# 14_FPGA_banks_7A_8A.net
KiCad netlist of a schematic drawn in Altium Designer
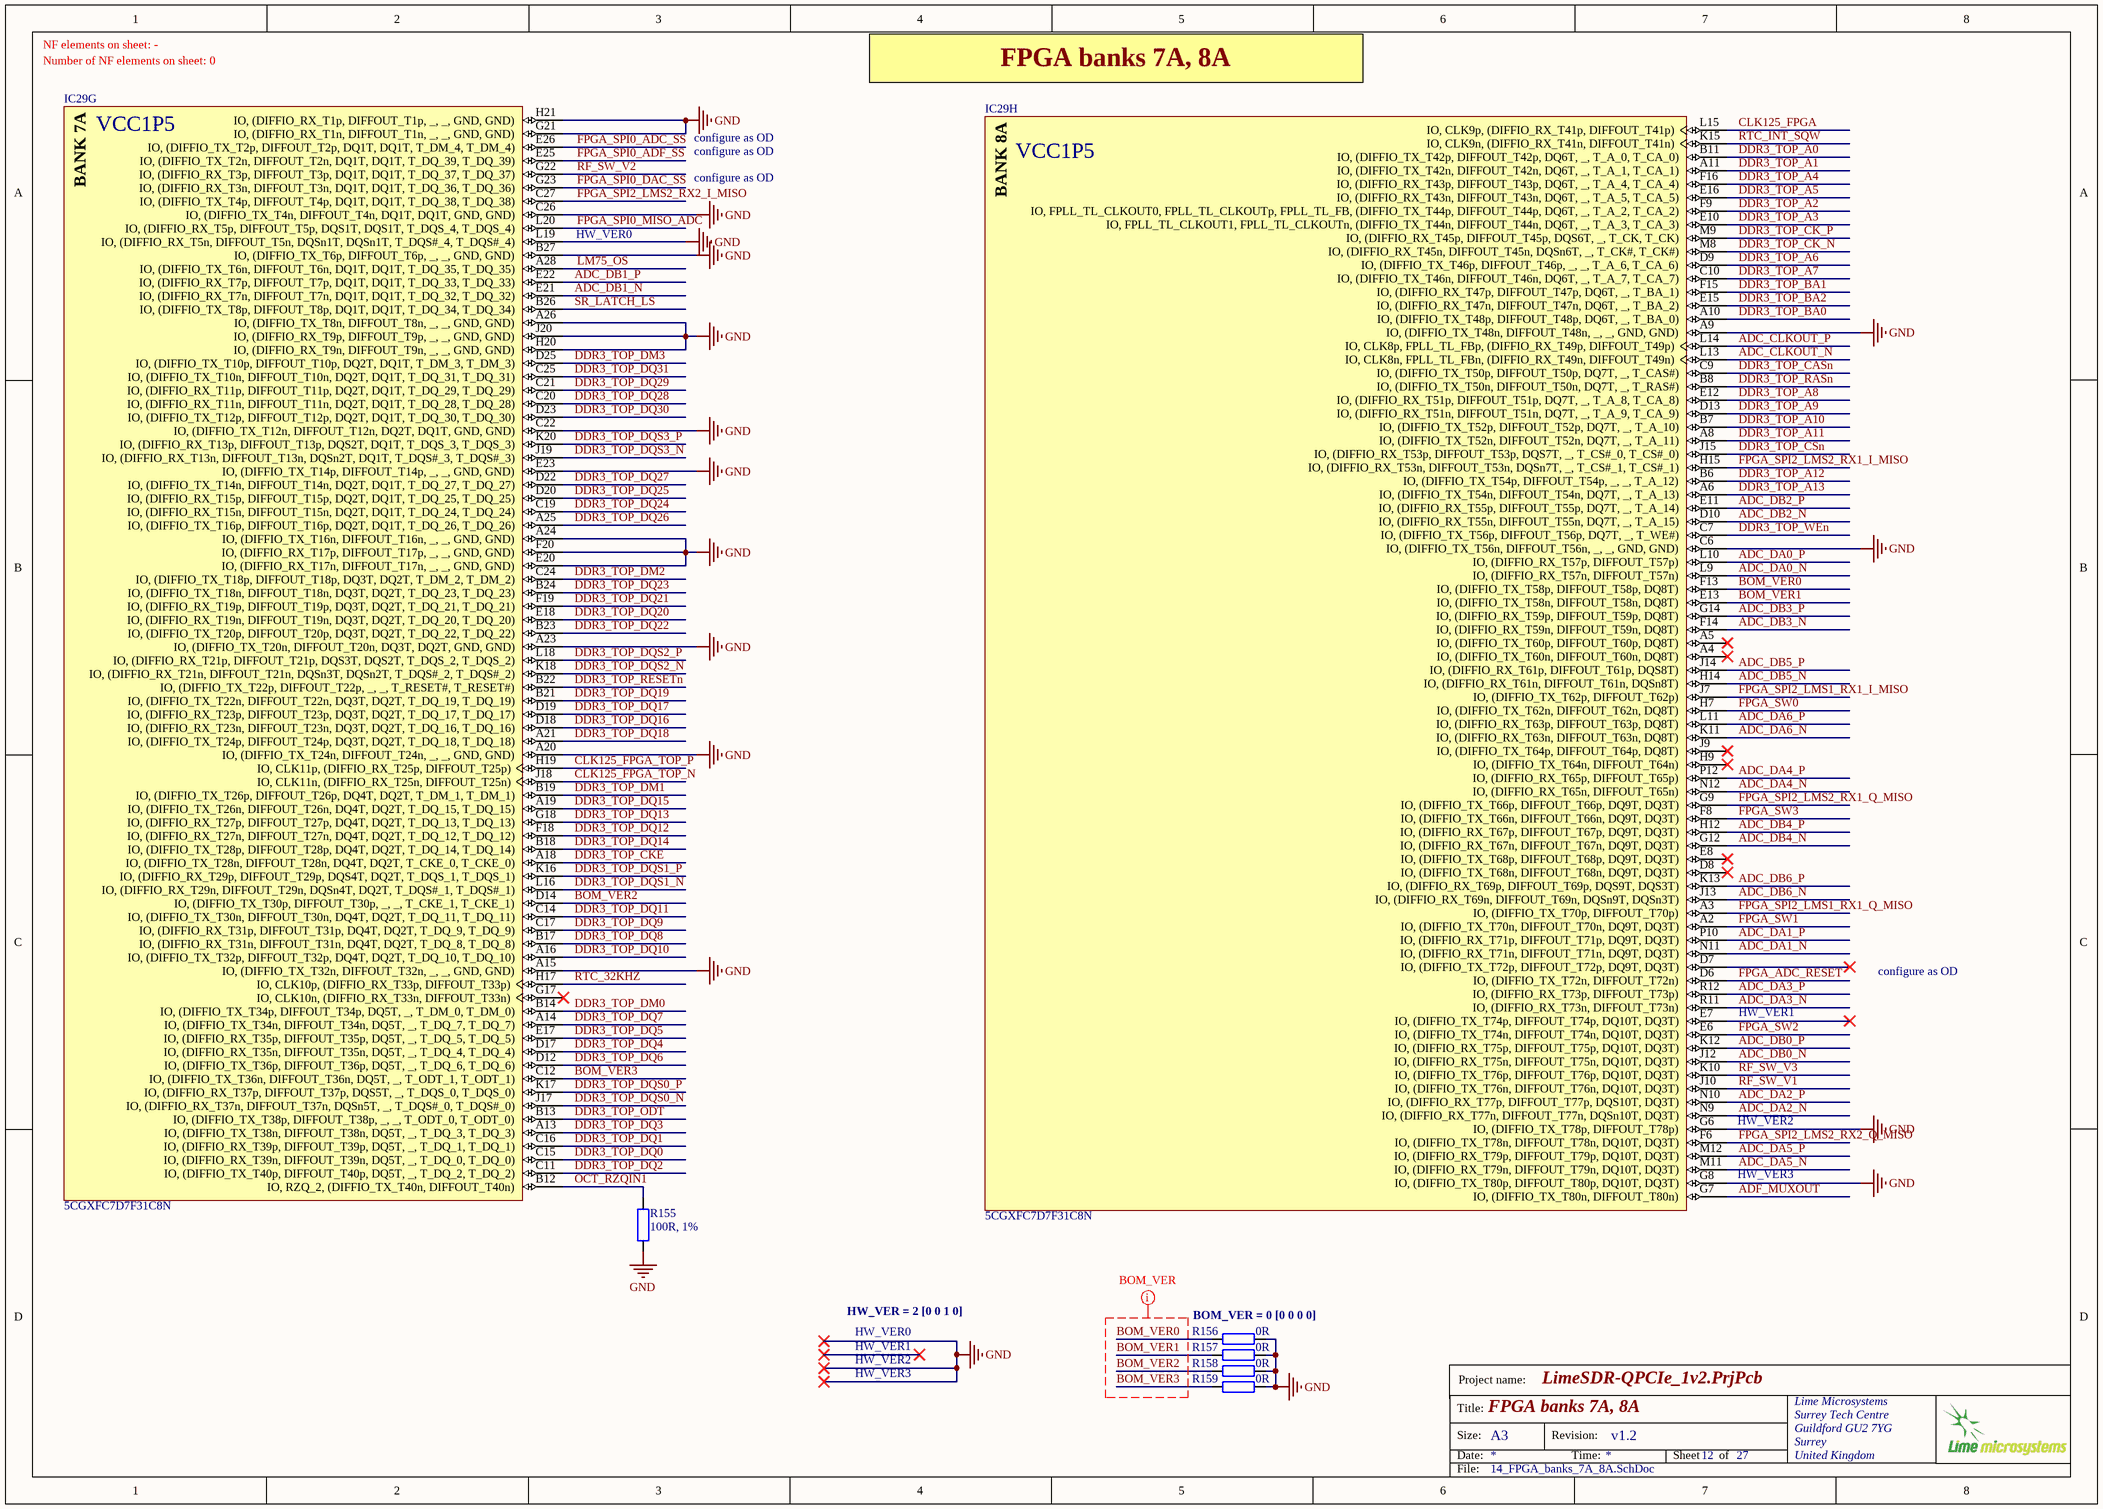
[diagram p0: 14_FPGA_banks_7A_8A.SchDoc]

(export (version "E")
  (design (tool "Eeschema 10.0.6"))
  (components
    (comp (ref "IC29")
      (value "5CGXFC7D7F31C8N")
      (footprint "ALTR-FBGA896_A-200")
      (fields (field (name "MANUFACTURER") "Altera"))
      (libsource (lib "LimeMicroAltiumLib_schLib") (part "5CGXFC7D7F31C8N"))
    )
    (comp (ref "R155")
      (value "100R, 1%")
      (footprint "RES0402")
      (fields (field (name "TOLERANCE") "±1%") (field (name "MANUFACTURER") "Stackpole Electronics Inc."))
      (libsource (lib "LimeFPGAboard_schLib") (part "Res_0402"))
    )
    (comp (ref "R156")
      (value "0R")
      (footprint "RES0402")
      (fields (field (name "MANUFACTURER") "Yageo"))
      (libsource (lib "LimeFPGAboard_schLib") (part "Res_0402"))
    )
    (comp (ref "R157")
      (value "0R")
      (footprint "RES0402")
      (fields (field (name "MANUFACTURER") "Yageo"))
      (libsource (lib "LimeFPGAboard_schLib") (part "Res_0402"))
    )
    (comp (ref "R158")
      (value "0R")
      (footprint "RES0402")
      (fields (field (name "MANUFACTURER") "Yageo"))
      (libsource (lib "LimeFPGAboard_schLib") (part "Res_0402"))
    )
    (comp (ref "R159")
      (value "0R")
      (footprint "RES0402")
      (fields (field (name "MANUFACTURER") "Yageo"))
      (libsource (lib "LimeFPGAboard_schLib") (part "Res_0402"))
    )
  )
  (nets
    (net (code "1") (name "/ADC_CLKOUT_N") (class "Default")
      (node (ref "IC29") (pin "L13") (pinfunction "IO,_CLK8n,_FPLL_TL_FBn,_(DIFFIO_RX_T49n,_DIFFOUT_T49n)_L13") (pintype "bidirectional"))
    )
    (net (code "2") (name "/ADC_CLKOUT_P") (class "Default")
      (node (ref "IC29") (pin "L14") (pinfunction "IO,_CLK8p,_FPLL_TL_FBp,_(DIFFIO_RX_T49p,_DIFFOUT_T49p)_L14") (pintype "bidirectional"))
    )
    (net (code "3") (name "/ADC_DA0_N") (class "Default")
      (node (ref "IC29") (pin "L9") (pinfunction "IO,_(DIFFIO_RX_T57n,_DIFFOUT_T57n)_L9") (pintype "bidirectional"))
    )
    (net (code "4") (name "/ADC_DA0_P") (class "Default")
      (node (ref "IC29") (pin "L10") (pinfunction "IO,_(DIFFIO_RX_T57p,_DIFFOUT_T57p)_L10") (pintype "bidirectional"))
    )
    (net (code "5") (name "/ADC_DA1_N") (class "Default")
      (node (ref "IC29") (pin "N11") (pinfunction "IO,_(DIFFIO_RX_T71n,_DIFFOUT_T71n,_DQ9T,_DQ3T)_N11") (pintype "bidirectional"))
    )
    (net (code "6") (name "/ADC_DA1_P") (class "Default")
      (node (ref "IC29") (pin "P10") (pinfunction "IO,_(DIFFIO_RX_T71p,_DIFFOUT_T71p,_DQ9T,_DQ3T)_P10") (pintype "bidirectional"))
    )
    (net (code "7") (name "/ADC_DA2_N") (class "Default")
      (node (ref "IC29") (pin "N9") (pinfunction "IO,_(DIFFIO_RX_T77n,_DIFFOUT_T77n,_DQSn10T,_DQ3T)_N9") (pintype "bidirectional"))
    )
    (net (code "8") (name "/ADC_DA2_P") (class "Default")
      (node (ref "IC29") (pin "N10") (pinfunction "IO,_(DIFFIO_RX_T77p,_DIFFOUT_T77p,_DQS10T,_DQ3T)_N10") (pintype "bidirectional"))
    )
    (net (code "9") (name "/ADC_DA3_N") (class "Default")
      (node (ref "IC29") (pin "R11") (pinfunction "IO,_(DIFFIO_RX_T73n,_DIFFOUT_T73n)_R11") (pintype "bidirectional"))
    )
    (net (code "10") (name "/ADC_DA3_P") (class "Default")
      (node (ref "IC29") (pin "R12") (pinfunction "IO,_(DIFFIO_RX_T73p,_DIFFOUT_T73p)_R12") (pintype "bidirectional"))
    )
    (net (code "11") (name "/ADC_DA4_N") (class "Default")
      (node (ref "IC29") (pin "N12") (pinfunction "IO,_(DIFFIO_RX_T65n,_DIFFOUT_T65n)_N12") (pintype "bidirectional"))
    )
    (net (code "12") (name "/ADC_DA4_P") (class "Default")
      (node (ref "IC29") (pin "P12") (pinfunction "IO,_(DIFFIO_RX_T65p,_DIFFOUT_T65p)_P12") (pintype "bidirectional"))
    )
    (net (code "13") (name "/ADC_DA5_N") (class "Default")
      (node (ref "IC29") (pin "M11") (pinfunction "IO,_(DIFFIO_RX_T79n,_DIFFOUT_T79n,_DQ10T,_DQ3T)_M11") (pintype "bidirectional"))
    )
    (net (code "14") (name "/ADC_DA5_P") (class "Default")
      (node (ref "IC29") (pin "M12") (pinfunction "IO,_(DIFFIO_RX_T79p,_DIFFOUT_T79p,_DQ10T,_DQ3T)_M12") (pintype "bidirectional"))
    )
    (net (code "15") (name "/ADC_DA6_N") (class "Default")
      (node (ref "IC29") (pin "K11") (pinfunction "IO,_(DIFFIO_RX_T63n,_DIFFOUT_T63n,_DQ8T)_K11") (pintype "bidirectional"))
    )
    (net (code "16") (name "/ADC_DA6_P") (class "Default")
      (node (ref "IC29") (pin "L11") (pinfunction "IO,_(DIFFIO_RX_T63p,_DIFFOUT_T63p,_DQ8T)_L11") (pintype "bidirectional"))
    )
    (net (code "17") (name "/ADC_DB0_N") (class "Default")
      (node (ref "IC29") (pin "J12") (pinfunction "IO,_(DIFFIO_RX_T75n,_DIFFOUT_T75n,_DQ10T,_DQ3T)_J12") (pintype "bidirectional"))
    )
    (net (code "18") (name "/ADC_DB0_P") (class "Default")
      (node (ref "IC29") (pin "K12") (pinfunction "IO,_(DIFFIO_RX_T75p,_DIFFOUT_T75p,_DQ10T,_DQ3T)_K12") (pintype "bidirectional"))
    )
    (net (code "19") (name "/ADC_DB1_N") (class "Default")
      (node (ref "IC29") (pin "E21") (pinfunction "IO,_(DIFFIO_RX_T7n,_DIFFOUT_T7n,_DQ1T,_DQ1T,_T_DQ_32,_T_DQ_32)_E21") (pintype "bidirectional"))
    )
    (net (code "20") (name "/ADC_DB1_P") (class "Default")
      (node (ref "IC29") (pin "E22") (pinfunction "IO,_(DIFFIO_RX_T7p,_DIFFOUT_T7p,_DQ1T,_DQ1T,_T_DQ_33,_T_DQ_33)_E22") (pintype "bidirectional"))
    )
    (net (code "21") (name "/ADC_DB2_N") (class "Default")
      (node (ref "IC29") (pin "D10") (pinfunction "IO,_(DIFFIO_RX_T55n,_DIFFOUT_T55n,_DQ7T,__,_T_A_15)_D10") (pintype "bidirectional"))
    )
    (net (code "22") (name "/ADC_DB2_P") (class "Default")
      (node (ref "IC29") (pin "E11") (pinfunction "IO,_(DIFFIO_RX_T55p,_DIFFOUT_T55p,_DQ7T,__,_T_A_14)_E11") (pintype "bidirectional"))
    )
    (net (code "23") (name "/ADC_DB3_N") (class "Default")
      (node (ref "IC29") (pin "F14") (pinfunction "IO,_(DIFFIO_RX_T59n,_DIFFOUT_T59n,_DQ8T)_F14") (pintype "bidirectional"))
    )
    (net (code "24") (name "/ADC_DB3_P") (class "Default")
      (node (ref "IC29") (pin "G14") (pinfunction "IO,_(DIFFIO_RX_T59p,_DIFFOUT_T59p,_DQ8T)_G14") (pintype "bidirectional"))
    )
    (net (code "25") (name "/ADC_DB4_N") (class "Default")
      (node (ref "IC29") (pin "G12") (pinfunction "IO,_(DIFFIO_RX_T67n,_DIFFOUT_T67n,_DQ9T,_DQ3T)_G12") (pintype "bidirectional"))
    )
    (net (code "26") (name "/ADC_DB4_P") (class "Default")
      (node (ref "IC29") (pin "H12") (pinfunction "IO,_(DIFFIO_RX_T67p,_DIFFOUT_T67p,_DQ9T,_DQ3T)_H12") (pintype "bidirectional"))
    )
    (net (code "27") (name "/ADC_DB5_N") (class "Default")
      (node (ref "IC29") (pin "H14") (pinfunction "IO,_(DIFFIO_RX_T61n,_DIFFOUT_T61n,_DQSn8T)_H14") (pintype "bidirectional"))
    )
    (net (code "28") (name "/ADC_DB5_P") (class "Default")
      (node (ref "IC29") (pin "J14") (pinfunction "IO,_(DIFFIO_RX_T61p,_DIFFOUT_T61p,_DQS8T)_J14") (pintype "bidirectional"))
    )
    (net (code "29") (name "/ADC_DB6_N") (class "Default")
      (node (ref "IC29") (pin "J13") (pinfunction "IO,_(DIFFIO_RX_T69n,_DIFFOUT_T69n,_DQSn9T,_DQSn3T)_J13") (pintype "bidirectional"))
    )
    (net (code "30") (name "/ADC_DB6_P") (class "Default")
      (node (ref "IC29") (pin "K13") (pinfunction "IO,_(DIFFIO_RX_T69p,_DIFFOUT_T69p,_DQS9T,_DQS3T)_K13") (pintype "bidirectional"))
    )
    (net (code "31") (name "/ADF_MUXOUT") (class "Default")
      (node (ref "IC29") (pin "G7") (pinfunction "IO,_(DIFFIO_TX_T80n,_DIFFOUT_T80n)_G7") (pintype "bidirectional"))
    )
    (net (code "32") (name "/BOM_VER0") (class "Default")
      (node (ref "IC29") (pin "F13") (pinfunction "IO,_(DIFFIO_TX_T58p,_DIFFOUT_T58p,_DQ8T)_F13") (pintype "bidirectional"))
      (node (ref "R156") (pin "1") (pinfunction "1_1") (pintype "passive"))
    )
    (net (code "33") (name "/BOM_VER1") (class "Default")
      (node (ref "IC29") (pin "E13") (pinfunction "IO,_(DIFFIO_TX_T58n,_DIFFOUT_T58n,_DQ8T)_E13") (pintype "bidirectional"))
      (node (ref "R157") (pin "1") (pinfunction "1_1") (pintype "passive"))
    )
    (net (code "34") (name "/BOM_VER2") (class "Default")
      (node (ref "IC29") (pin "D14") (pinfunction "IO,_(DIFFIO_TX_T30p,_DIFFOUT_T30p,__,__,_T_CKE_1,_T_CKE_1)_D14") (pintype "bidirectional"))
      (node (ref "R158") (pin "1") (pinfunction "1_1") (pintype "passive"))
    )
    (net (code "35") (name "/BOM_VER3") (class "Default")
      (node (ref "IC29") (pin "C12") (pinfunction "IO,_(DIFFIO_TX_T36n,_DIFFOUT_T36n,_DQ5T,__,_T_ODT_1,_T_ODT_1)_C12") (pintype "bidirectional"))
      (node (ref "R159") (pin "1") (pinfunction "1_1") (pintype "passive"))
    )
    (net (code "36") (name "/CLK125_FPGA") (class "Default")
      (node (ref "IC29") (pin "L15") (pinfunction "IO,_CLK9p,_(DIFFIO_RX_T41p,_DIFFOUT_T41p)_L15") (pintype "bidirectional"))
    )
    (net (code "37") (name "/CLK125_FPGA_TOP_N") (class "Default")
      (node (ref "IC29") (pin "J18") (pinfunction "IO,_CLK11n,_(DIFFIO_RX_T25n,_DIFFOUT_T25n)_J18") (pintype "bidirectional"))
    )
    (net (code "38") (name "/CLK125_FPGA_TOP_P") (class "Default")
      (node (ref "IC29") (pin "H19") (pinfunction "IO,_CLK11p,_(DIFFIO_RX_T25p,_DIFFOUT_T25p)_H19") (pintype "bidirectional"))
    )
    (net (code "39") (name "/DDR3_TOP_A0") (class "Default")
      (node (ref "IC29") (pin "B11") (pinfunction "IO,_(DIFFIO_TX_T42p,_DIFFOUT_T42p,_DQ6T,__,_T_A_0,_T_CA_0)_B11") (pintype "bidirectional"))
    )
    (net (code "40") (name "/DDR3_TOP_A1") (class "Default")
      (node (ref "IC29") (pin "A11") (pinfunction "IO,_(DIFFIO_TX_T42n,_DIFFOUT_T42n,_DQ6T,__,_T_A_1,_T_CA_1)_A11") (pintype "bidirectional"))
    )
    (net (code "41") (name "/DDR3_TOP_A2") (class "Default")
      (node (ref "IC29") (pin "F9") (pinfunction "IO,_FPLL_TL_CLKOUT0,_FPLL_TL_CLKOUTp,_FPLL_TL_FB,_(DIFFIO_TX_T44p,_DIFFOUT_T44p,_DQ6T,__,_T_A_2,_T_CA_2)_F9") (pintype "bidirectional"))
    )
    (net (code "42") (name "/DDR3_TOP_A3") (class "Default")
      (node (ref "IC29") (pin "E10") (pinfunction "IO,_FPLL_TL_CLKOUT1,_FPLL_TL_CLKOUTn,_(DIFFIO_TX_T44n,_DIFFOUT_T44n,_DQ6T,__,_T_A_3,_T_CA_3)_E10") (pintype "bidirectional"))
    )
    (net (code "43") (name "/DDR3_TOP_A4") (class "Default")
      (node (ref "IC29") (pin "F16") (pinfunction "IO,_(DIFFIO_RX_T43p,_DIFFOUT_T43p,_DQ6T,__,_T_A_4,_T_CA_4)_F16") (pintype "bidirectional"))
    )
    (net (code "44") (name "/DDR3_TOP_A5") (class "Default")
      (node (ref "IC29") (pin "E16") (pinfunction "IO,_(DIFFIO_RX_T43n,_DIFFOUT_T43n,_DQ6T,__,_T_A_5,_T_CA_5)_E16") (pintype "bidirectional"))
    )
    (net (code "45") (name "/DDR3_TOP_A6") (class "Default")
      (node (ref "IC29") (pin "D9") (pinfunction "IO,_(DIFFIO_TX_T46p,_DIFFOUT_T46p,__,__,_T_A_6,_T_CA_6)_D9") (pintype "bidirectional"))
    )
    (net (code "46") (name "/DDR3_TOP_A7") (class "Default")
      (node (ref "IC29") (pin "C10") (pinfunction "IO,_(DIFFIO_TX_T46n,_DIFFOUT_T46n,_DQ6T,__,_T_A_7,_T_CA_7)_C10") (pintype "bidirectional"))
    )
    (net (code "47") (name "/DDR3_TOP_A8") (class "Default")
      (node (ref "IC29") (pin "E12") (pinfunction "IO,_(DIFFIO_RX_T51p,_DIFFOUT_T51p,_DQ7T,__,_T_A_8,_T_CA_8)_E12") (pintype "bidirectional"))
    )
    (net (code "48") (name "/DDR3_TOP_A9") (class "Default")
      (node (ref "IC29") (pin "D13") (pinfunction "IO,_(DIFFIO_RX_T51n,_DIFFOUT_T51n,_DQ7T,__,_T_A_9,_T_CA_9)_D13") (pintype "bidirectional"))
    )
    (net (code "49") (name "/DDR3_TOP_A10") (class "Default")
      (node (ref "IC29") (pin "B7") (pinfunction "IO,_(DIFFIO_TX_T52p,_DIFFOUT_T52p,_DQ7T,__,_T_A_10)_B7") (pintype "bidirectional"))
    )
    (net (code "50") (name "/DDR3_TOP_A11") (class "Default")
      (node (ref "IC29") (pin "A8") (pinfunction "IO,_(DIFFIO_TX_T52n,_DIFFOUT_T52n,_DQ7T,__,_T_A_11)_A8") (pintype "bidirectional"))
    )
    (net (code "51") (name "/DDR3_TOP_A12") (class "Default")
      (node (ref "IC29") (pin "B6") (pinfunction "IO,_(DIFFIO_TX_T54p,_DIFFOUT_T54p,__,__,_T_A_12)_B6") (pintype "bidirectional"))
    )
    (net (code "52") (name "/DDR3_TOP_A13") (class "Default")
      (node (ref "IC29") (pin "A6") (pinfunction "IO,_(DIFFIO_TX_T54n,_DIFFOUT_T54n,_DQ7T,__,_T_A_13)_A6") (pintype "bidirectional"))
    )
    (net (code "53") (name "/DDR3_TOP_BA0") (class "Default")
      (node (ref "IC29") (pin "A10") (pinfunction "IO,_(DIFFIO_TX_T48p,_DIFFOUT_T48p,_DQ6T,__,_T_BA_0)_A10") (pintype "bidirectional"))
    )
    (net (code "54") (name "/DDR3_TOP_BA1") (class "Default")
      (node (ref "IC29") (pin "F15") (pinfunction "IO,_(DIFFIO_RX_T47p,_DIFFOUT_T47p,_DQ6T,__,_T_BA_1)_F15") (pintype "bidirectional"))
    )
    (net (code "55") (name "/DDR3_TOP_BA2") (class "Default")
      (node (ref "IC29") (pin "E15") (pinfunction "IO,_(DIFFIO_RX_T47n,_DIFFOUT_T47n,_DQ6T,__,_T_BA_2)_E15") (pintype "bidirectional"))
    )
    (net (code "56") (name "/DDR3_TOP_CASn") (class "Default")
      (node (ref "IC29") (pin "C9") (pinfunction "IO,_(DIFFIO_TX_T50p,_DIFFOUT_T50p,_DQ7T,__,_T_CAS#)_C9") (pintype "bidirectional"))
    )
    (net (code "57") (name "/DDR3_TOP_CKE") (class "Default")
      (node (ref "IC29") (pin "A18") (pinfunction "IO,_(DIFFIO_TX_T28n,_DIFFOUT_T28n,_DQ4T,_DQ2T,_T_CKE_0,_T_CKE_0)_A18") (pintype "bidirectional"))
    )
    (net (code "58") (name "/DDR3_TOP_CK_N") (class "Default")
      (node (ref "IC29") (pin "M8") (pinfunction "IO,_(DIFFIO_RX_T45n,_DIFFOUT_T45n,_DQSn6T,__,_T_CK#,_T_CK#)_M8") (pintype "bidirectional"))
    )
    (net (code "59") (name "/DDR3_TOP_CK_P") (class "Default")
      (node (ref "IC29") (pin "M9") (pinfunction "IO,_(DIFFIO_RX_T45p,_DIFFOUT_T45p,_DQS6T,__,_T_CK,_T_CK)_M9") (pintype "bidirectional"))
    )
    (net (code "60") (name "/DDR3_TOP_CSn") (class "Default")
      (node (ref "IC29") (pin "J15") (pinfunction "IO,_(DIFFIO_RX_T53p,_DIFFOUT_T53p,_DQS7T,__,_T_CS#_0,_T_CS#_0)_J15") (pintype "bidirectional"))
    )
    (net (code "61") (name "/DDR3_TOP_DM0") (class "Default")
      (node (ref "IC29") (pin "B14") (pinfunction "IO,_(DIFFIO_TX_T34p,_DIFFOUT_T34p,_DQ5T,__,_T_DM_0,_T_DM_0)_B14") (pintype "bidirectional"))
    )
    (net (code "62") (name "/DDR3_TOP_DM1") (class "Default")
      (node (ref "IC29") (pin "B19") (pinfunction "IO,_(DIFFIO_TX_T26p,_DIFFOUT_T26p,_DQ4T,_DQ2T,_T_DM_1,_T_DM_1)_B19") (pintype "bidirectional"))
    )
    (net (code "63") (name "/DDR3_TOP_DM2") (class "Default")
      (node (ref "IC29") (pin "C24") (pinfunction "IO,_(DIFFIO_TX_T18p,_DIFFOUT_T18p,_DQ3T,_DQ2T,_T_DM_2,_T_DM_2)_C24") (pintype "bidirectional"))
    )
    (net (code "64") (name "/DDR3_TOP_DM3") (class "Default")
      (node (ref "IC29") (pin "D25") (pinfunction "IO,_(DIFFIO_TX_T10p,_DIFFOUT_T10p,_DQ2T,_DQ1T,_T_DM_3,_T_DM_3)_D25") (pintype "bidirectional"))
    )
    (net (code "65") (name "/DDR3_TOP_DQ0") (class "Default")
      (node (ref "IC29") (pin "C15") (pinfunction "IO,_(DIFFIO_RX_T39n,_DIFFOUT_T39n,_DQ5T,__,_T_DQ_0,_T_DQ_0)_C15") (pintype "bidirectional"))
    )
    (net (code "66") (name "/DDR3_TOP_DQ1") (class "Default")
      (node (ref "IC29") (pin "C16") (pinfunction "IO,_(DIFFIO_RX_T39p,_DIFFOUT_T39p,_DQ5T,__,_T_DQ_1,_T_DQ_1)_C16") (pintype "bidirectional"))
    )
    (net (code "67") (name "/DDR3_TOP_DQ2") (class "Default")
      (node (ref "IC29") (pin "C11") (pinfunction "IO,_(DIFFIO_TX_T40p,_DIFFOUT_T40p,_DQ5T,__,_T_DQ_2,_T_DQ_2)_C11") (pintype "bidirectional"))
    )
    (net (code "68") (name "/DDR3_TOP_DQ3") (class "Default")
      (node (ref "IC29") (pin "A13") (pinfunction "IO,_(DIFFIO_TX_T38n,_DIFFOUT_T38n,_DQ5T,__,_T_DQ_3,_T_DQ_3)_A13") (pintype "bidirectional"))
    )
    (net (code "69") (name "/DDR3_TOP_DQ4") (class "Default")
      (node (ref "IC29") (pin "D17") (pinfunction "IO,_(DIFFIO_RX_T35n,_DIFFOUT_T35n,_DQ5T,__,_T_DQ_4,_T_DQ_4)_D17") (pintype "bidirectional"))
    )
    (net (code "70") (name "/DDR3_TOP_DQ5") (class "Default")
      (node (ref "IC29") (pin "E17") (pinfunction "IO,_(DIFFIO_RX_T35p,_DIFFOUT_T35p,_DQ5T,__,_T_DQ_5,_T_DQ_5)_E17") (pintype "bidirectional"))
    )
    (net (code "71") (name "/DDR3_TOP_DQ6") (class "Default")
      (node (ref "IC29") (pin "D12") (pinfunction "IO,_(DIFFIO_TX_T36p,_DIFFOUT_T36p,_DQ5T,__,_T_DQ_6,_T_DQ_6)_D12") (pintype "bidirectional"))
    )
    (net (code "72") (name "/DDR3_TOP_DQ7") (class "Default")
      (node (ref "IC29") (pin "A14") (pinfunction "IO,_(DIFFIO_TX_T34n,_DIFFOUT_T34n,_DQ5T,__,_T_DQ_7,_T_DQ_7)_A14") (pintype "bidirectional"))
    )
    (net (code "73") (name "/DDR3_TOP_DQ8") (class "Default")
      (node (ref "IC29") (pin "B17") (pinfunction "IO,_(DIFFIO_RX_T31n,_DIFFOUT_T31n,_DQ4T,_DQ2T,_T_DQ_8,_T_DQ_8)_B17") (pintype "bidirectional"))
    )
    (net (code "74") (name "/DDR3_TOP_DQ9") (class "Default")
      (node (ref "IC29") (pin "C17") (pinfunction "IO,_(DIFFIO_RX_T31p,_DIFFOUT_T31p,_DQ4T,_DQ2T,_T_DQ_9,_T_DQ_9)_C17") (pintype "bidirectional"))
    )
    (net (code "75") (name "/DDR3_TOP_DQ10") (class "Default")
      (node (ref "IC29") (pin "A16") (pinfunction "IO,_(DIFFIO_TX_T32p,_DIFFOUT_T32p,_DQ4T,_DQ2T,_T_DQ_10,_T_DQ_10)_A16") (pintype "bidirectional"))
    )
    (net (code "76") (name "/DDR3_TOP_DQ11") (class "Default")
      (node (ref "IC29") (pin "C14") (pinfunction "IO,_(DIFFIO_TX_T30n,_DIFFOUT_T30n,_DQ4T,_DQ2T,_T_DQ_11,_T_DQ_11)_C14") (pintype "bidirectional"))
    )
    (net (code "77") (name "/DDR3_TOP_DQ12") (class "Default")
      (node (ref "IC29") (pin "F18") (pinfunction "IO,_(DIFFIO_RX_T27n,_DIFFOUT_T27n,_DQ4T,_DQ2T,_T_DQ_12,_T_DQ_12)_F18") (pintype "bidirectional"))
    )
    (net (code "78") (name "/DDR3_TOP_DQ13") (class "Default")
      (node (ref "IC29") (pin "G18") (pinfunction "IO,_(DIFFIO_RX_T27p,_DIFFOUT_T27p,_DQ4T,_DQ2T,_T_DQ_13,_T_DQ_13)_G18") (pintype "bidirectional"))
    )
    (net (code "79") (name "/DDR3_TOP_DQ14") (class "Default")
      (node (ref "IC29") (pin "B18") (pinfunction "IO,_(DIFFIO_TX_T28p,_DIFFOUT_T28p,_DQ4T,_DQ2T,_T_DQ_14,_T_DQ_14)_B18") (pintype "bidirectional"))
    )
    (net (code "80") (name "/DDR3_TOP_DQ15") (class "Default")
      (node (ref "IC29") (pin "A19") (pinfunction "IO,_(DIFFIO_TX_T26n,_DIFFOUT_T26n,_DQ4T,_DQ2T,_T_DQ_15,_T_DQ_15)_A19") (pintype "bidirectional"))
    )
    (net (code "81") (name "/DDR3_TOP_DQ16") (class "Default")
      (node (ref "IC29") (pin "D18") (pinfunction "IO,_(DIFFIO_RX_T23n,_DIFFOUT_T23n,_DQ3T,_DQ2T,_T_DQ_16,_T_DQ_16)_D18") (pintype "bidirectional"))
    )
    (net (code "82") (name "/DDR3_TOP_DQ17") (class "Default")
      (node (ref "IC29") (pin "D19") (pinfunction "IO,_(DIFFIO_RX_T23p,_DIFFOUT_T23p,_DQ3T,_DQ2T,_T_DQ_17,_T_DQ_17)_D19") (pintype "bidirectional"))
    )
    (net (code "83") (name "/DDR3_TOP_DQ18") (class "Default")
      (node (ref "IC29") (pin "A21") (pinfunction "IO,_(DIFFIO_TX_T24p,_DIFFOUT_T24p,_DQ3T,_DQ2T,_T_DQ_18,_T_DQ_18)_A21") (pintype "bidirectional"))
    )
    (net (code "84") (name "/DDR3_TOP_DQ19") (class "Default")
      (node (ref "IC29") (pin "B21") (pinfunction "IO,_(DIFFIO_TX_T22n,_DIFFOUT_T22n,_DQ3T,_DQ2T,_T_DQ_19,_T_DQ_19)_B21") (pintype "bidirectional"))
    )
    (net (code "85") (name "/DDR3_TOP_DQ20") (class "Default")
      (node (ref "IC29") (pin "E18") (pinfunction "IO,_(DIFFIO_RX_T19n,_DIFFOUT_T19n,_DQ3T,_DQ2T,_T_DQ_20,_T_DQ_20)_E18") (pintype "bidirectional"))
    )
    (net (code "86") (name "/DDR3_TOP_DQ21") (class "Default")
      (node (ref "IC29") (pin "F19") (pinfunction "IO,_(DIFFIO_RX_T19p,_DIFFOUT_T19p,_DQ3T,_DQ2T,_T_DQ_21,_T_DQ_21)_F19") (pintype "bidirectional"))
    )
    (net (code "87") (name "/DDR3_TOP_DQ22") (class "Default")
      (node (ref "IC29") (pin "B23") (pinfunction "IO,_(DIFFIO_TX_T20p,_DIFFOUT_T20p,_DQ3T,_DQ2T,_T_DQ_22,_T_DQ_22)_B23") (pintype "bidirectional"))
    )
    (net (code "88") (name "/DDR3_TOP_DQ23") (class "Default")
      (node (ref "IC29") (pin "B24") (pinfunction "IO,_(DIFFIO_TX_T18n,_DIFFOUT_T18n,_DQ3T,_DQ2T,_T_DQ_23,_T_DQ_23)_B24") (pintype "bidirectional"))
    )
    (net (code "89") (name "/DDR3_TOP_DQ24") (class "Default")
      (node (ref "IC29") (pin "C19") (pinfunction "IO,_(DIFFIO_RX_T15n,_DIFFOUT_T15n,_DQ2T,_DQ1T,_T_DQ_24,_T_DQ_24)_C19") (pintype "bidirectional"))
    )
    (net (code "90") (name "/DDR3_TOP_DQ25") (class "Default")
      (node (ref "IC29") (pin "D20") (pinfunction "IO,_(DIFFIO_RX_T15p,_DIFFOUT_T15p,_DQ2T,_DQ1T,_T_DQ_25,_T_DQ_25)_D20") (pintype "bidirectional"))
    )
    (net (code "91") (name "/DDR3_TOP_DQ26") (class "Default")
      (node (ref "IC29") (pin "A25") (pinfunction "IO,_(DIFFIO_TX_T16p,_DIFFOUT_T16p,_DQ2T,_DQ1T,_T_DQ_26,_T_DQ_26)_A25") (pintype "bidirectional"))
    )
    (net (code "92") (name "/DDR3_TOP_DQ27") (class "Default")
      (node (ref "IC29") (pin "D22") (pinfunction "IO,_(DIFFIO_TX_T14n,_DIFFOUT_T14n,_DQ2T,_DQ1T,_T_DQ_27,_T_DQ_27)_D22") (pintype "bidirectional"))
    )
    (net (code "93") (name "/DDR3_TOP_DQ28") (class "Default")
      (node (ref "IC29") (pin "C20") (pinfunction "IO,_(DIFFIO_RX_T11n,_DIFFOUT_T11n,_DQ2T,_DQ1T,_T_DQ_28,_T_DQ_28)_C20") (pintype "bidirectional"))
    )
    (net (code "94") (name "/DDR3_TOP_DQ29") (class "Default")
      (node (ref "IC29") (pin "C21") (pinfunction "IO,_(DIFFIO_RX_T11p,_DIFFOUT_T11p,_DQ2T,_DQ1T,_T_DQ_29,_T_DQ_29)_C21") (pintype "bidirectional"))
    )
    (net (code "95") (name "/DDR3_TOP_DQ30") (class "Default")
      (node (ref "IC29") (pin "D23") (pinfunction "IO,_(DIFFIO_TX_T12p,_DIFFOUT_T12p,_DQ2T,_DQ1T,_T_DQ_30,_T_DQ_30)_D23") (pintype "bidirectional"))
    )
    (net (code "96") (name "/DDR3_TOP_DQ31") (class "Default")
      (node (ref "IC29") (pin "C25") (pinfunction "IO,_(DIFFIO_TX_T10n,_DIFFOUT_T10n,_DQ2T,_DQ1T,_T_DQ_31,_T_DQ_31)_C25") (pintype "bidirectional"))
    )
    (net (code "97") (name "/DDR3_TOP_DQS0_N") (class "Default")
      (node (ref "IC29") (pin "J17") (pinfunction "IO,_(DIFFIO_RX_T37n,_DIFFOUT_T37n,_DQSn5T,__,_T_DQS#_0,_T_DQS#_0)_J17") (pintype "bidirectional"))
    )
    (net (code "98") (name "/DDR3_TOP_DQS0_P") (class "Default")
      (node (ref "IC29") (pin "K17") (pinfunction "IO,_(DIFFIO_RX_T37p,_DIFFOUT_T37p,_DQS5T,__,_T_DQS_0,_T_DQS_0)_K17") (pintype "bidirectional"))
    )
    (net (code "99") (name "/DDR3_TOP_DQS1_N") (class "Default")
      (node (ref "IC29") (pin "L16") (pinfunction "IO,_(DIFFIO_RX_T29n,_DIFFOUT_T29n,_DQSn4T,_DQ2T,_T_DQS#_1,_T_DQS#_1)_L16") (pintype "bidirectional"))
    )
    (net (code "100") (name "/DDR3_TOP_DQS1_P") (class "Default")
      (node (ref "IC29") (pin "K16") (pinfunction "IO,_(DIFFIO_RX_T29p,_DIFFOUT_T29p,_DQS4T,_DQ2T,_T_DQS_1,_T_DQS_1)_K16") (pintype "bidirectional"))
    )
    (net (code "101") (name "/DDR3_TOP_DQS2_N") (class "Default")
      (node (ref "IC29") (pin "K18") (pinfunction "IO,_(DIFFIO_RX_T21n,_DIFFOUT_T21n,_DQSn3T,_DQSn2T,_T_DQS#_2,_T_DQS#_2)_K18") (pintype "bidirectional"))
    )
    (net (code "102") (name "/DDR3_TOP_DQS2_P") (class "Default")
      (node (ref "IC29") (pin "L18") (pinfunction "IO,_(DIFFIO_RX_T21p,_DIFFOUT_T21p,_DQS3T,_DQS2T,_T_DQS_2,_T_DQS_2)_L18") (pintype "bidirectional"))
    )
    (net (code "103") (name "/DDR3_TOP_DQS3_N") (class "Default")
      (node (ref "IC29") (pin "J19") (pinfunction "IO,_(DIFFIO_RX_T13n,_DIFFOUT_T13n,_DQSn2T,_DQ1T,_T_DQS#_3,_T_DQS#_3)_J19") (pintype "bidirectional"))
    )
    (net (code "104") (name "/DDR3_TOP_DQS3_P") (class "Default")
      (node (ref "IC29") (pin "K20") (pinfunction "IO,_(DIFFIO_RX_T13p,_DIFFOUT_T13p,_DQS2T,_DQ1T,_T_DQS_3,_T_DQS_3)_K20") (pintype "bidirectional"))
    )
    (net (code "105") (name "/DDR3_TOP_ODT") (class "Default")
      (node (ref "IC29") (pin "B13") (pinfunction "IO,_(DIFFIO_TX_T38p,_DIFFOUT_T38p,__,__,_T_ODT_0,_T_ODT_0)_B13") (pintype "bidirectional"))
    )
    (net (code "106") (name "/DDR3_TOP_RASn") (class "Default")
      (node (ref "IC29") (pin "B8") (pinfunction "IO,_(DIFFIO_TX_T50n,_DIFFOUT_T50n,_DQ7T,__,_T_RAS#)_B8") (pintype "bidirectional"))
    )
    (net (code "107") (name "/DDR3_TOP_RESETn") (class "Default")
      (node (ref "IC29") (pin "B22") (pinfunction "IO,_(DIFFIO_TX_T22p,_DIFFOUT_T22p,__,__,_T_RESET#,_T_RESET#)_B22") (pintype "bidirectional"))
    )
    (net (code "108") (name "/DDR3_TOP_WEn") (class "Default")
      (node (ref "IC29") (pin "C7") (pinfunction "IO,_(DIFFIO_TX_T56p,_DIFFOUT_T56p,_DQ7T,__,_T_WE#)_C7") (pintype "bidirectional"))
    )
    (net (code "109") (name "/FPGA_ADC_RESET") (class "Default")
      (node (ref "IC29") (pin "D6") (pinfunction "IO,_(DIFFIO_TX_T72n,_DIFFOUT_T72n)_D6") (pintype "bidirectional"))
    )
    (net (code "110") (name "/FPGA_SPI0_ADC_SS") (class "Default")
      (node (ref "IC29") (pin "E26") (pinfunction "IO,_(DIFFIO_TX_T2p,_DIFFOUT_T2p,_DQ1T,_DQ1T,_T_DM_4,_T_DM_4)_E26") (pintype "bidirectional"))
    )
    (net (code "111") (name "/FPGA_SPI0_ADF_SS") (class "Default")
      (node (ref "IC29") (pin "E25") (pinfunction "IO,_(DIFFIO_TX_T2n,_DIFFOUT_T2n,_DQ1T,_DQ1T,_T_DQ_39,_T_DQ_39)_E25") (pintype "bidirectional"))
    )
    (net (code "112") (name "/FPGA_SPI0_DAC_SS") (class "Default")
      (node (ref "IC29") (pin "G23") (pinfunction "IO,_(DIFFIO_RX_T3n,_DIFFOUT_T3n,_DQ1T,_DQ1T,_T_DQ_36,_T_DQ_36)_G23") (pintype "bidirectional"))
    )
    (net (code "113") (name "/FPGA_SPI0_MISO_ADC") (class "Default")
      (node (ref "IC29") (pin "L20") (pinfunction "IO,_(DIFFIO_RX_T5p,_DIFFOUT_T5p,_DQS1T,_DQS1T,_T_DQS_4,_T_DQS_4)_L20") (pintype "bidirectional"))
    )
    (net (code "114") (name "/FPGA_SPI2_LMS1_RX1_I_MISO") (class "Default")
      (node (ref "IC29") (pin "J7") (pinfunction "IO,_(DIFFIO_TX_T62p,_DIFFOUT_T62p)_J7") (pintype "bidirectional"))
    )
    (net (code "115") (name "/FPGA_SPI2_LMS1_RX1_Q_MISO") (class "Default")
      (node (ref "IC29") (pin "A3") (pinfunction "IO,_(DIFFIO_TX_T70p,_DIFFOUT_T70p)_A3") (pintype "bidirectional"))
    )
    (net (code "116") (name "/FPGA_SPI2_LMS2_RX1_I_MISO") (class "Default")
      (node (ref "IC29") (pin "H15") (pinfunction "IO,_(DIFFIO_RX_T53n,_DIFFOUT_T53n,_DQSn7T,__,_T_CS#_1,_T_CS#_1)_H15") (pintype "bidirectional"))
    )
    (net (code "117") (name "/FPGA_SPI2_LMS2_RX1_Q_MISO") (class "Default")
      (node (ref "IC29") (pin "G9") (pinfunction "IO,_(DIFFIO_TX_T66p,_DIFFOUT_T66p,_DQ9T,_DQ3T)_G9") (pintype "bidirectional"))
    )
    (net (code "118") (name "/FPGA_SPI2_LMS2_RX2_I_MISO") (class "Default")
      (node (ref "IC29") (pin "C27") (pinfunction "IO,_(DIFFIO_TX_T4p,_DIFFOUT_T4p,_DQ1T,_DQ1T,_T_DQ_38,_T_DQ_38)_C27") (pintype "bidirectional"))
    )
    (net (code "119") (name "/FPGA_SPI2_LMS2_RX2_Q_MISO") (class "Default")
      (node (ref "IC29") (pin "F6") (pinfunction "IO,_(DIFFIO_TX_T78n,_DIFFOUT_T78n,_DQ10T,_DQ3T)_F6") (pintype "bidirectional"))
    )
    (net (code "120") (name "/FPGA_SW0") (class "Default")
      (node (ref "IC29") (pin "H7") (pinfunction "IO,_(DIFFIO_TX_T62n,_DIFFOUT_T62n,_DQ8T)_H7") (pintype "bidirectional"))
    )
    (net (code "121") (name "/FPGA_SW1") (class "Default")
      (node (ref "IC29") (pin "A2") (pinfunction "IO,_(DIFFIO_TX_T70n,_DIFFOUT_T70n,_DQ9T,_DQ3T)_A2") (pintype "bidirectional"))
    )
    (net (code "122") (name "/FPGA_SW2") (class "Default")
      (node (ref "IC29") (pin "E6") (pinfunction "IO,_(DIFFIO_TX_T74n,_DIFFOUT_T74n,_DQ10T,_DQ3T)_E6") (pintype "bidirectional"))
    )
    (net (code "123") (name "/FPGA_SW3") (class "Default")
      (node (ref "IC29") (pin "F8") (pinfunction "IO,_(DIFFIO_TX_T66n,_DIFFOUT_T66n,_DQ9T,_DQ3T)_F8") (pintype "bidirectional"))
    )
    (net (code "124") (name "/LM75_OS") (class "Default")
      (node (ref "IC29") (pin "A28") (pinfunction "IO,_(DIFFIO_TX_T6n,_DIFFOUT_T6n,_DQ1T,_DQ1T,_T_DQ_35,_T_DQ_35)_A28") (pintype "bidirectional"))
    )
    (net (code "125") (name "/OCT_RZQIN1") (class "Default")
      (node (ref "IC29") (pin "B12") (pinfunction "IO,_RZQ_2,_(DIFFIO_TX_T40n,_DIFFOUT_T40n)_B12") (pintype "bidirectional"))
      (node (ref "R155") (pin "2") (pinfunction "2_2") (pintype "passive"))
    )
    (net (code "126") (name "/RF_SW_V1") (class "Default")
      (node (ref "IC29") (pin "J10") (pinfunction "IO,_(DIFFIO_TX_T76n,_DIFFOUT_T76n,_DQ10T,_DQ3T)_J10") (pintype "bidirectional"))
    )
    (net (code "127") (name "/RF_SW_V2") (class "Default")
      (node (ref "IC29") (pin "G22") (pinfunction "IO,_(DIFFIO_RX_T3p,_DIFFOUT_T3p,_DQ1T,_DQ1T,_T_DQ_37,_T_DQ_37)_G22") (pintype "bidirectional"))
    )
    (net (code "128") (name "/RF_SW_V3") (class "Default")
      (node (ref "IC29") (pin "K10") (pinfunction "IO,_(DIFFIO_TX_T76p,_DIFFOUT_T76p,_DQ10T,_DQ3T)_K10") (pintype "bidirectional"))
    )
    (net (code "129") (name "/RTC_32KHZ") (class "Default")
      (node (ref "IC29") (pin "H17") (pinfunction "IO,_CLK10p,_(DIFFIO_RX_T33p,_DIFFOUT_T33p)_H17") (pintype "bidirectional"))
    )
    (net (code "130") (name "/RTC_INT_SQW") (class "Default")
      (node (ref "IC29") (pin "K15") (pinfunction "IO,_CLK9n,_(DIFFIO_RX_T41n,_DIFFOUT_T41n)_K15") (pintype "bidirectional"))
    )
    (net (code "131") (name "/SR_LATCH_LS") (class "Default")
      (node (ref "IC29") (pin "B26") (pinfunction "IO,_(DIFFIO_TX_T8p,_DIFFOUT_T8p,_DQ1T,_DQ1T,_T_DQ_34,_T_DQ_34)_B26") (pintype "bidirectional"))
    )
    (net (code "132") (name "GND") (class "Default")
      (node (ref "IC29") (pin "A15") (pinfunction "IO,_(DIFFIO_TX_T32n,_DIFFOUT_T32n,__,__,_GND,_GND)_A15") (pintype "bidirectional"))
      (node (ref "IC29") (pin "A20") (pinfunction "IO,_(DIFFIO_TX_T24n,_DIFFOUT_T24n,__,__,_GND,_GND)_A20") (pintype "bidirectional"))
      (node (ref "IC29") (pin "A23") (pinfunction "IO,_(DIFFIO_TX_T20n,_DIFFOUT_T20n,_DQ3T,_DQ2T,_GND,_GND)_A23") (pintype "bidirectional"))
      (node (ref "IC29") (pin "A24") (pinfunction "IO,_(DIFFIO_TX_T16n,_DIFFOUT_T16n,__,__,_GND,_GND)_A24") (pintype "bidirectional"))
      (node (ref "IC29") (pin "A26") (pinfunction "IO,_(DIFFIO_TX_T8n,_DIFFOUT_T8n,__,__,_GND,_GND)_A26") (pintype "bidirectional"))
      (node (ref "IC29") (pin "A9") (pinfunction "IO,_(DIFFIO_TX_T48n,_DIFFOUT_T48n,__,__,_GND,_GND)_A9") (pintype "bidirectional"))
      (node (ref "IC29") (pin "B27") (pinfunction "IO,_(DIFFIO_TX_T6p,_DIFFOUT_T6p,__,__,_GND,_GND)_B27") (pintype "bidirectional"))
      (node (ref "IC29") (pin "C22") (pinfunction "IO,_(DIFFIO_TX_T12n,_DIFFOUT_T12n,_DQ2T,_DQ1T,_GND,_GND)_C22") (pintype "bidirectional"))
      (node (ref "IC29") (pin "C26") (pinfunction "IO,_(DIFFIO_TX_T4n,_DIFFOUT_T4n,_DQ1T,_DQ1T,_GND,_GND)_C26") (pintype "bidirectional"))
      (node (ref "IC29") (pin "C6") (pinfunction "IO,_(DIFFIO_TX_T56n,_DIFFOUT_T56n,__,__,_GND,_GND)_C6") (pintype "bidirectional"))
      (node (ref "IC29") (pin "E20") (pinfunction "IO,_(DIFFIO_RX_T17n,_DIFFOUT_T17n,__,__,_GND,_GND)_E20") (pintype "bidirectional"))
      (node (ref "IC29") (pin "E23") (pinfunction "IO,_(DIFFIO_TX_T14p,_DIFFOUT_T14p,__,__,_GND,_GND)_E23") (pintype "bidirectional"))
      (node (ref "IC29") (pin "F20") (pinfunction "IO,_(DIFFIO_RX_T17p,_DIFFOUT_T17p,__,__,_GND,_GND)_F20") (pintype "bidirectional"))
      (node (ref "IC29") (pin "G21") (pinfunction "IO,_(DIFFIO_RX_T1n,_DIFFOUT_T1n,__,__,_GND,_GND)_G21") (pintype "bidirectional"))
      (node (ref "IC29") (pin "G6") (pinfunction "IO,_(DIFFIO_TX_T78p,_DIFFOUT_T78p)_G6") (pintype "bidirectional"))
      (node (ref "IC29") (pin "G8") (pinfunction "IO,_(DIFFIO_TX_T80p,_DIFFOUT_T80p,_DQ10T,_DQ3T)_G8") (pintype "bidirectional"))
      (node (ref "IC29") (pin "H20") (pinfunction "IO,_(DIFFIO_RX_T9n,_DIFFOUT_T9n,__,__,_GND,_GND)_H20") (pintype "bidirectional"))
      (node (ref "IC29") (pin "H21") (pinfunction "IO,_(DIFFIO_RX_T1p,_DIFFOUT_T1p,__,__,_GND,_GND)_H21") (pintype "bidirectional"))
      (node (ref "IC29") (pin "J20") (pinfunction "IO,_(DIFFIO_RX_T9p,_DIFFOUT_T9p,__,__,_GND,_GND)_J20") (pintype "bidirectional"))
      (node (ref "IC29") (pin "L19") (pinfunction "IO,_(DIFFIO_RX_T5n,_DIFFOUT_T5n,_DQSn1T,_DQSn1T,_T_DQS#_4,_T_DQS#_4)_L19") (pintype "bidirectional"))
      (node (ref "R155") (pin "1") (pinfunction "1_1") (pintype "passive"))
      (node (ref "R156") (pin "2") (pinfunction "2_2") (pintype "passive"))
      (node (ref "R157") (pin "2") (pinfunction "2_2") (pintype "passive"))
      (node (ref "R158") (pin "2") (pinfunction "2_2") (pintype "passive"))
      (node (ref "R159") (pin "2") (pinfunction "2_2") (pintype "passive"))
    )
    (net (code "133") (name "unconnected-(IC29G-IO,_CLK10n,_(DIFFIO_RX_T33n,_DIFFOUT_T33n)-PadG17)") (class "Default")
      (node (ref "IC29") (pin "G17") (pinfunction "IO,_CLK10n,_(DIFFIO_RX_T33n,_DIFFOUT_T33n)_G17") (pintype "bidirectional+no_connect"))
    )
    (net (code "134") (name "unconnected-(IC29H-IO,_(DIFFIO_TX_T60n,_DIFFOUT_T60n,_DQ8T)-PadA4)") (class "Default")
      (node (ref "IC29") (pin "A4") (pinfunction "IO,_(DIFFIO_TX_T60n,_DIFFOUT_T60n,_DQ8T)_A4") (pintype "bidirectional+no_connect"))
    )
    (net (code "135") (name "unconnected-(IC29H-IO,_(DIFFIO_TX_T60p,_DIFFOUT_T60p,_DQ8T)-PadA5)") (class "Default")
      (node (ref "IC29") (pin "A5") (pinfunction "IO,_(DIFFIO_TX_T60p,_DIFFOUT_T60p,_DQ8T)_A5") (pintype "bidirectional+no_connect"))
    )
    (net (code "136") (name "unconnected-(IC29H-IO,_(DIFFIO_TX_T64n,_DIFFOUT_T64n)-PadH9)") (class "Default")
      (node (ref "IC29") (pin "H9") (pinfunction "IO,_(DIFFIO_TX_T64n,_DIFFOUT_T64n)_H9") (pintype "bidirectional+no_connect"))
    )
    (net (code "137") (name "unconnected-(IC29H-IO,_(DIFFIO_TX_T64p,_DIFFOUT_T64p,_DQ8T)-PadJ9)") (class "Default")
      (node (ref "IC29") (pin "J9") (pinfunction "IO,_(DIFFIO_TX_T64p,_DIFFOUT_T64p,_DQ8T)_J9") (pintype "bidirectional+no_connect"))
    )
    (net (code "138") (name "unconnected-(IC29H-IO,_(DIFFIO_TX_T68n,_DIFFOUT_T68n,_DQ9T,_DQ3T)-PadD8)") (class "Default")
      (node (ref "IC29") (pin "D8") (pinfunction "IO,_(DIFFIO_TX_T68n,_DIFFOUT_T68n,_DQ9T,_DQ3T)_D8") (pintype "bidirectional+no_connect"))
    )
    (net (code "139") (name "unconnected-(IC29H-IO,_(DIFFIO_TX_T68p,_DIFFOUT_T68p,_DQ9T,_DQ3T)-PadE8)") (class "Default")
      (node (ref "IC29") (pin "E8") (pinfunction "IO,_(DIFFIO_TX_T68p,_DIFFOUT_T68p,_DQ9T,_DQ3T)_E8") (pintype "bidirectional+no_connect"))
    )
    (net (code "140") (name "unconnected-(IC29H-IO,_(DIFFIO_TX_T72p,_DIFFOUT_T72p,_DQ9T,_DQ3T)-PadD7)") (class "Default")
      (node (ref "IC29") (pin "D7") (pinfunction "IO,_(DIFFIO_TX_T72p,_DIFFOUT_T72p,_DQ9T,_DQ3T)_D7") (pintype "bidirectional+no_connect"))
    )
    (net (code "141") (name "unconnected-(IC29H-IO,_(DIFFIO_TX_T74p,_DIFFOUT_T74p,_DQ10T,_DQ3T)-PadE7)") (class "Default")
      (node (ref "IC29") (pin "E7") (pinfunction "IO,_(DIFFIO_TX_T74p,_DIFFOUT_T74p,_DQ10T,_DQ3T)_E7") (pintype "bidirectional+no_connect"))
    )
  )
)
